# differential-buffer-quadchannel.net
KiCad netlist of a schematic drawn in EAGLE
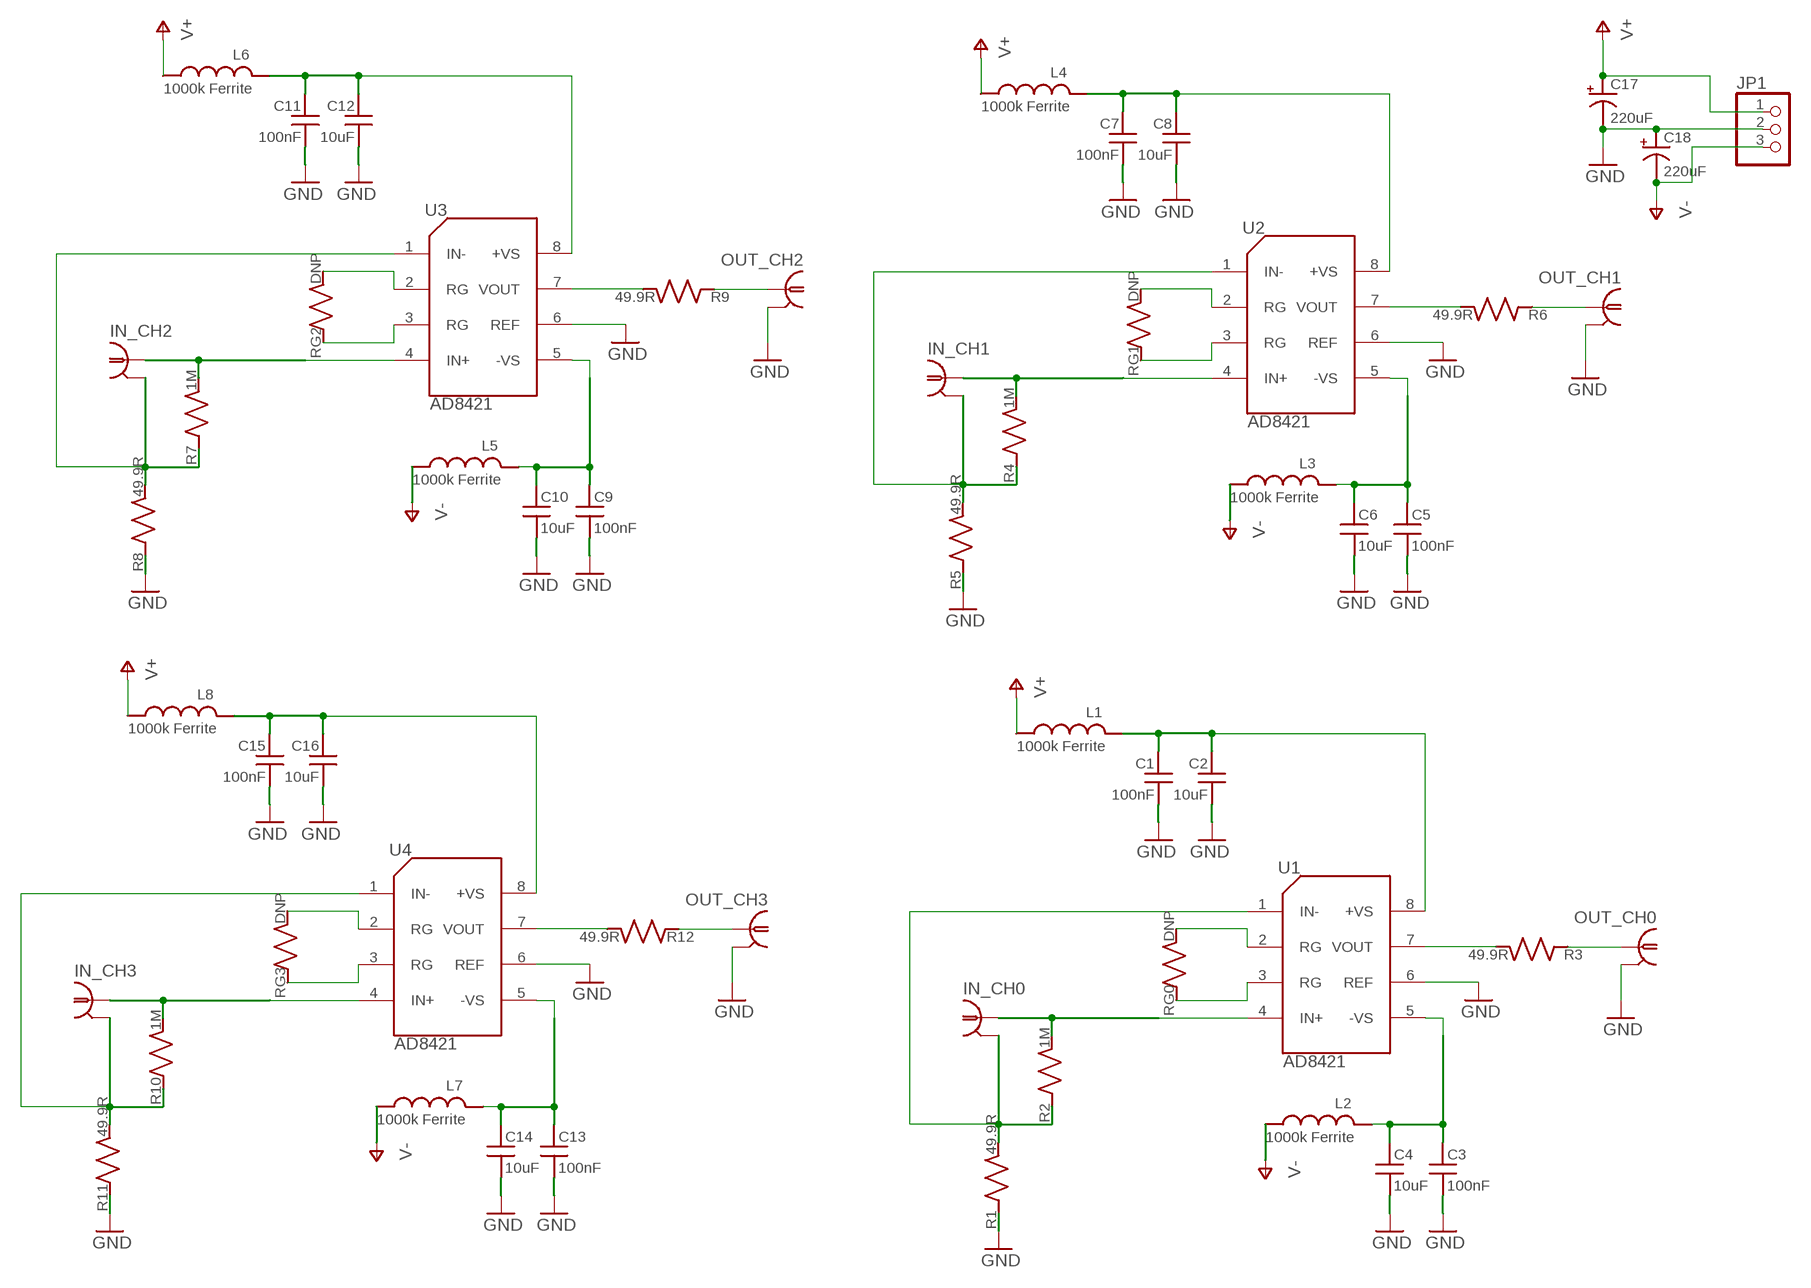
[diagram p0: schematic, sheet 1]

(export (version "E")
  (design (tool "Eeschema 10.0.6"))
  (components
    (comp (ref "C1")
      (value "100nF")
      (footprint "eagle-import:C_MLCC_0603")
      (fields (field (name "PARTNO") "1276-1936-1-ND"))
      (libsource (lib "eagle-import") (part "C_MLCC_SMDCMLCC_0603"))
    )
    (comp (ref "C2")
      (value "10uF")
      (footprint "eagle-import:C_MLCC_0805")
      (fields (field (name "PARTNO") "445-14417-1-ND"))
      (libsource (lib "eagle-import") (part "C_MLCC_SMDCMLCC_0805"))
    )
    (comp (ref "C3")
      (value "100nF")
      (footprint "eagle-import:C_MLCC_0603")
      (fields (field (name "PARTNO") "1276-1936-1-ND"))
      (libsource (lib "eagle-import") (part "C_MLCC_SMDCMLCC_0603"))
    )
    (comp (ref "C4")
      (value "10uF")
      (footprint "eagle-import:C_MLCC_0805")
      (fields (field (name "PARTNO") "445-14417-1-ND"))
      (libsource (lib "eagle-import") (part "C_MLCC_SMDCMLCC_0805"))
    )
    (comp (ref "C5")
      (value "100nF")
      (footprint "eagle-import:C_MLCC_0603")
      (fields (field (name "PARTNO") "1276-1936-1-ND"))
      (libsource (lib "eagle-import") (part "C_MLCC_SMDCMLCC_0603"))
    )
    (comp (ref "C6")
      (value "10uF")
      (footprint "eagle-import:C_MLCC_0805")
      (fields (field (name "PARTNO") "445-14417-1-ND"))
      (libsource (lib "eagle-import") (part "C_MLCC_SMDCMLCC_0805"))
    )
    (comp (ref "C7")
      (value "100nF")
      (footprint "eagle-import:C_MLCC_0603")
      (fields (field (name "PARTNO") "1276-1936-1-ND"))
      (libsource (lib "eagle-import") (part "C_MLCC_SMDCMLCC_0603"))
    )
    (comp (ref "C8")
      (value "10uF")
      (footprint "eagle-import:C_MLCC_0805")
      (fields (field (name "PARTNO") "445-14417-1-ND"))
      (libsource (lib "eagle-import") (part "C_MLCC_SMDCMLCC_0805"))
    )
    (comp (ref "C9")
      (value "100nF")
      (footprint "eagle-import:C_MLCC_0603")
      (fields (field (name "PARTNO") "1276-1936-1-ND"))
      (libsource (lib "eagle-import") (part "C_MLCC_SMDCMLCC_0603"))
    )
    (comp (ref "C10")
      (value "10uF")
      (footprint "eagle-import:C_MLCC_0805")
      (fields (field (name "PARTNO") "445-14417-1-ND"))
      (libsource (lib "eagle-import") (part "C_MLCC_SMDCMLCC_0805"))
    )
    (comp (ref "C11")
      (value "100nF")
      (footprint "eagle-import:C_MLCC_0603")
      (fields (field (name "PARTNO") "1276-1936-1-ND"))
      (libsource (lib "eagle-import") (part "C_MLCC_SMDCMLCC_0603"))
    )
    (comp (ref "C12")
      (value "10uF")
      (footprint "eagle-import:C_MLCC_0805")
      (fields (field (name "PARTNO") "445-14417-1-ND"))
      (libsource (lib "eagle-import") (part "C_MLCC_SMDCMLCC_0805"))
    )
    (comp (ref "C13")
      (value "100nF")
      (footprint "eagle-import:C_MLCC_0603")
      (fields (field (name "PARTNO") "1276-1936-1-ND"))
      (libsource (lib "eagle-import") (part "C_MLCC_SMDCMLCC_0603"))
    )
    (comp (ref "C14")
      (value "10uF")
      (footprint "eagle-import:C_MLCC_0805")
      (fields (field (name "PARTNO") "445-14417-1-ND"))
      (libsource (lib "eagle-import") (part "C_MLCC_SMDCMLCC_0805"))
    )
    (comp (ref "C15")
      (value "100nF")
      (footprint "eagle-import:C_MLCC_0603")
      (fields (field (name "PARTNO") "1276-1936-1-ND"))
      (libsource (lib "eagle-import") (part "C_MLCC_SMDCMLCC_0603"))
    )
    (comp (ref "C16")
      (value "10uF")
      (footprint "eagle-import:C_MLCC_0805")
      (fields (field (name "PARTNO") "445-14417-1-ND"))
      (libsource (lib "eagle-import") (part "C_MLCC_SMDCMLCC_0805"))
    )
    (comp (ref "C17")
      (value "220uF")
      (footprint "eagle-import:PANASONIC_F")
      (fields (field (name "PARTNO") "PCE3955CT-ND"))
      (libsource (lib "eagle-import") (part "C_POL_SMDF"))
    )
    (comp (ref "C18")
      (value "220uF")
      (footprint "eagle-import:PANASONIC_F")
      (fields (field (name "PARTNO") "PCE3955CT-ND"))
      (libsource (lib "eagle-import") (part "C_POL_SMDF"))
    )
    (comp (ref "IN_CH0")
      (value "BNC-V")
      (footprint "eagle-import:BNC-V")
      (libsource (lib "eagle-import") (part "BNC-V"))
    )
    (comp (ref "IN_CH1")
      (value "BNC-V")
      (footprint "eagle-import:BNC-V")
      (libsource (lib "eagle-import") (part "BNC-V"))
    )
    (comp (ref "IN_CH2")
      (value "BNC-V")
      (footprint "eagle-import:BNC-V")
      (libsource (lib "eagle-import") (part "BNC-V"))
    )
    (comp (ref "IN_CH3")
      (value "BNC-V")
      (footprint "eagle-import:BNC-V")
      (libsource (lib "eagle-import") (part "BNC-V"))
    )
    (comp (ref "JP1")
      (value "PINHD-1X3")
      (footprint "eagle-import:1X03")
      (fields (field (name "PARTNO") "WM4201-ND"))
      (libsource (lib "eagle-import") (part "PINHD-1X3"))
    )
    (comp (ref "L1")
      (value "1000k Ferrite")
      (footprint "eagle-import:L_FERRITE_0603")
      (fields (field (name "PARTNO") "445-1548-1-ND"))
      (libsource (lib "eagle-import") (part "L_FERRITE_SMDLFERRITE_0603"))
    )
    (comp (ref "L2")
      (value "1000k Ferrite")
      (footprint "eagle-import:L_FERRITE_0603")
      (fields (field (name "PARTNO") "445-1548-1-ND"))
      (libsource (lib "eagle-import") (part "L_FERRITE_SMDLFERRITE_0603"))
    )
    (comp (ref "L3")
      (value "1000k Ferrite")
      (footprint "eagle-import:L_FERRITE_0603")
      (fields (field (name "PARTNO") "445-1548-1-ND"))
      (libsource (lib "eagle-import") (part "L_FERRITE_SMDLFERRITE_0603"))
    )
    (comp (ref "L4")
      (value "1000k Ferrite")
      (footprint "eagle-import:L_FERRITE_0603")
      (fields (field (name "PARTNO") "445-1548-1-ND"))
      (libsource (lib "eagle-import") (part "L_FERRITE_SMDLFERRITE_0603"))
    )
    (comp (ref "L5")
      (value "1000k Ferrite")
      (footprint "eagle-import:L_FERRITE_0603")
      (fields (field (name "PARTNO") "445-1548-1-ND"))
      (libsource (lib "eagle-import") (part "L_FERRITE_SMDLFERRITE_0603"))
    )
    (comp (ref "L6")
      (value "1000k Ferrite")
      (footprint "eagle-import:L_FERRITE_0603")
      (fields (field (name "PARTNO") "445-1548-1-ND"))
      (libsource (lib "eagle-import") (part "L_FERRITE_SMDLFERRITE_0603"))
    )
    (comp (ref "L7")
      (value "1000k Ferrite")
      (footprint "eagle-import:L_FERRITE_0603")
      (fields (field (name "PARTNO") "445-1548-1-ND"))
      (libsource (lib "eagle-import") (part "L_FERRITE_SMDLFERRITE_0603"))
    )
    (comp (ref "L8")
      (value "1000k Ferrite")
      (footprint "eagle-import:L_FERRITE_0603")
      (fields (field (name "PARTNO") "445-1548-1-ND"))
      (libsource (lib "eagle-import") (part "L_FERRITE_SMDLFERRITE_0603"))
    )
    (comp (ref "OUT_CH0")
      (value "BNC-V")
      (footprint "eagle-import:BNC-V")
      (libsource (lib "eagle-import") (part "BNC-V"))
    )
    (comp (ref "OUT_CH1")
      (value "BNC-V")
      (footprint "eagle-import:BNC-V")
      (libsource (lib "eagle-import") (part "BNC-V"))
    )
    (comp (ref "OUT_CH2")
      (value "BNC-V")
      (footprint "eagle-import:BNC-V")
      (libsource (lib "eagle-import") (part "BNC-V"))
    )
    (comp (ref "OUT_CH3")
      (value "BNC-V")
      (footprint "eagle-import:BNC-V")
      (libsource (lib "eagle-import") (part "BNC-V"))
    )
    (comp (ref "R1")
      (value "49.9R")
      (footprint "eagle-import:R_0603")
      (fields (field (name "PARTNO") "P49.9HCT-ND"))
      (libsource (lib "eagle-import") (part "jqi_passives_R_SMDR0603"))
    )
    (comp (ref "R2")
      (value "1M")
      (footprint "eagle-import:R_0603")
      (fields (field (name "PARTNO") "P1.00MHCT-ND"))
      (libsource (lib "eagle-import") (part "R_SMDR0603"))
    )
    (comp (ref "R3")
      (value "49.9R")
      (footprint "eagle-import:R_0603")
      (fields (field (name "PARTNO") "P49.9HCT-ND"))
      (libsource (lib "eagle-import") (part "jqi_passives_R_SMDR0603"))
    )
    (comp (ref "R4")
      (value "1M")
      (footprint "eagle-import:R_0603")
      (fields (field (name "PARTNO") "P1.00MHCT-ND"))
      (libsource (lib "eagle-import") (part "R_SMDR0603"))
    )
    (comp (ref "R5")
      (value "49.9R")
      (footprint "eagle-import:R_0603")
      (fields (field (name "PARTNO") "P49.9HCT-ND"))
      (libsource (lib "eagle-import") (part "jqi_passives_R_SMDR0603"))
    )
    (comp (ref "R6")
      (value "49.9R")
      (footprint "eagle-import:R_0603")
      (fields (field (name "PARTNO") "P49.9HCT-ND"))
      (libsource (lib "eagle-import") (part "jqi_passives_R_SMDR0603"))
    )
    (comp (ref "R7")
      (value "1M")
      (footprint "eagle-import:R_0603")
      (fields (field (name "PARTNO") "P1.00MHCT-ND"))
      (libsource (lib "eagle-import") (part "R_SMDR0603"))
    )
    (comp (ref "R8")
      (value "49.9R")
      (footprint "eagle-import:R_0603")
      (fields (field (name "PARTNO") "P49.9HCT-ND"))
      (libsource (lib "eagle-import") (part "jqi_passives_R_SMDR0603"))
    )
    (comp (ref "R9")
      (value "49.9R")
      (footprint "eagle-import:R_0603")
      (fields (field (name "PARTNO") "P49.9HCT-ND"))
      (libsource (lib "eagle-import") (part "jqi_passives_R_SMDR0603"))
    )
    (comp (ref "R10")
      (value "1M")
      (footprint "eagle-import:R_0603")
      (fields (field (name "PARTNO") "P1.00MHCT-ND"))
      (libsource (lib "eagle-import") (part "R_SMDR0603"))
    )
    (comp (ref "R11")
      (value "49.9R")
      (footprint "eagle-import:R_0603")
      (fields (field (name "PARTNO") "P49.9HCT-ND"))
      (libsource (lib "eagle-import") (part "jqi_passives_R_SMDR0603"))
    )
    (comp (ref "R12")
      (value "49.9R")
      (footprint "eagle-import:R_0603")
      (fields (field (name "PARTNO") "P49.9HCT-ND"))
      (libsource (lib "eagle-import") (part "jqi_passives_R_SMDR0603"))
    )
    (comp (ref "RG0")
      (value "DNP")
      (footprint "eagle-import:R_0402")
      (libsource (lib "eagle-import") (part "jqi_passives_R_SMDR0402"))
    )
    (comp (ref "RG1")
      (value "DNP")
      (footprint "eagle-import:R_0402")
      (libsource (lib "eagle-import") (part "jqi_passives_R_SMDR0402"))
    )
    (comp (ref "RG2")
      (value "DNP")
      (footprint "eagle-import:R_0402")
      (libsource (lib "eagle-import") (part "jqi_passives_R_SMDR0402"))
    )
    (comp (ref "RG3")
      (value "DNP")
      (footprint "eagle-import:R_0402")
      (libsource (lib "eagle-import") (part "jqi_passives_R_SMDR0402"))
    )
    (comp (ref "U1")
      (value "AD8421")
      (footprint "eagle-import:SOIC-8")
      (fields (field (name "PARTNO") "AD8421ARZ-R7CT-ND"))
      (libsource (lib "eagle-import") (part "AD8421"))
    )
    (comp (ref "U2")
      (value "AD8421")
      (footprint "eagle-import:SOIC-8")
      (fields (field (name "PARTNO") "AD8421ARZ-R7CT-ND"))
      (libsource (lib "eagle-import") (part "AD8421"))
    )
    (comp (ref "U3")
      (value "AD8421")
      (footprint "eagle-import:SOIC-8")
      (fields (field (name "PARTNO") "AD8421ARZ-R7CT-ND"))
      (libsource (lib "eagle-import") (part "AD8421"))
    )
    (comp (ref "U4")
      (value "AD8421")
      (footprint "eagle-import:SOIC-8")
      (fields (field (name "PARTNO") "AD8421ARZ-R7CT-ND"))
      (libsource (lib "eagle-import") (part "AD8421"))
    )
  )
  (nets
    (net (code "1") (name "GND") (class "Default")
      (node (ref "C1") (pin "P$2") (pinfunction "2_P$2") (pintype "passive"))
      (node (ref "C10") (pin "P$2") (pinfunction "2_P$2") (pintype "passive"))
      (node (ref "C11") (pin "P$2") (pinfunction "2_P$2") (pintype "passive"))
      (node (ref "C12") (pin "P$2") (pinfunction "2_P$2") (pintype "passive"))
      (node (ref "C13") (pin "P$2") (pinfunction "2_P$2") (pintype "passive"))
      (node (ref "C14") (pin "P$2") (pinfunction "2_P$2") (pintype "passive"))
      (node (ref "C15") (pin "P$2") (pinfunction "2_P$2") (pintype "passive"))
      (node (ref "C16") (pin "P$2") (pinfunction "2_P$2") (pintype "passive"))
      (node (ref "C17") (pin "-") (pinfunction "-_-") (pintype "passive"))
      (node (ref "C18") (pin "+") (pinfunction "+_+") (pintype "passive"))
      (node (ref "C2") (pin "P$2") (pinfunction "2_P$2") (pintype "passive"))
      (node (ref "C3") (pin "P$2") (pinfunction "2_P$2") (pintype "passive"))
      (node (ref "C4") (pin "P$2") (pinfunction "2_P$2") (pintype "passive"))
      (node (ref "C5") (pin "P$2") (pinfunction "2_P$2") (pintype "passive"))
      (node (ref "C6") (pin "P$2") (pinfunction "2_P$2") (pintype "passive"))
      (node (ref "C7") (pin "P$2") (pinfunction "2_P$2") (pintype "passive"))
      (node (ref "C8") (pin "P$2") (pinfunction "2_P$2") (pintype "passive"))
      (node (ref "C9") (pin "P$2") (pinfunction "2_P$2") (pintype "passive"))
      (node (ref "JP1") (pin "2") (pinfunction "2_2") (pintype "passive"))
      (node (ref "OUT_CH0") (pin "2") (pinfunction "2_2") (pintype "passive"))
      (node (ref "OUT_CH1") (pin "2") (pinfunction "2_2") (pintype "passive"))
      (node (ref "OUT_CH2") (pin "2") (pinfunction "2_2") (pintype "passive"))
      (node (ref "OUT_CH3") (pin "2") (pinfunction "2_2") (pintype "passive"))
      (node (ref "R1") (pin "P$1") (pinfunction "1_P$1") (pintype "passive"))
      (node (ref "R11") (pin "P$1") (pinfunction "1_P$1") (pintype "passive"))
      (node (ref "R5") (pin "P$1") (pinfunction "1_P$1") (pintype "passive"))
      (node (ref "R8") (pin "P$1") (pinfunction "1_P$1") (pintype "passive"))
      (node (ref "U1") (pin "6") (pinfunction "REF_6") (pintype "bidirectional"))
      (node (ref "U2") (pin "6") (pinfunction "REF_6") (pintype "bidirectional"))
      (node (ref "U3") (pin "6") (pinfunction "REF_6") (pintype "bidirectional"))
      (node (ref "U4") (pin "6") (pinfunction "REF_6") (pintype "bidirectional"))
    )
    (net (code "2") (name "Net-(C1-1)") (class "Default")
      (node (ref "C1") (pin "P$1") (pinfunction "1_P$1") (pintype "passive"))
      (node (ref "C2") (pin "P$1") (pinfunction "1_P$1") (pintype "passive"))
      (node (ref "L1") (pin "P$1") (pinfunction "1_P$1") (pintype "passive"))
      (node (ref "U1") (pin "8") (pinfunction "+VS_8") (pintype "bidirectional"))
    )
    (net (code "3") (name "Net-(C3-1)") (class "Default")
      (node (ref "C3") (pin "P$1") (pinfunction "1_P$1") (pintype "passive"))
      (node (ref "C4") (pin "P$1") (pinfunction "1_P$1") (pintype "passive"))
      (node (ref "L2") (pin "P$1") (pinfunction "1_P$1") (pintype "passive"))
      (node (ref "U1") (pin "5") (pinfunction "-VS_5") (pintype "bidirectional"))
    )
    (net (code "4") (name "Net-(C5-1)") (class "Default")
      (node (ref "C5") (pin "P$1") (pinfunction "1_P$1") (pintype "passive"))
      (node (ref "C6") (pin "P$1") (pinfunction "1_P$1") (pintype "passive"))
      (node (ref "L3") (pin "P$1") (pinfunction "1_P$1") (pintype "passive"))
      (node (ref "U2") (pin "5") (pinfunction "-VS_5") (pintype "bidirectional"))
    )
    (net (code "5") (name "Net-(C7-1)") (class "Default")
      (node (ref "C7") (pin "P$1") (pinfunction "1_P$1") (pintype "passive"))
      (node (ref "C8") (pin "P$1") (pinfunction "1_P$1") (pintype "passive"))
      (node (ref "L4") (pin "P$1") (pinfunction "1_P$1") (pintype "passive"))
      (node (ref "U2") (pin "8") (pinfunction "+VS_8") (pintype "bidirectional"))
    )
    (net (code "6") (name "Net-(C10-1)") (class "Default")
      (node (ref "C10") (pin "P$1") (pinfunction "1_P$1") (pintype "passive"))
      (node (ref "C9") (pin "P$1") (pinfunction "1_P$1") (pintype "passive"))
      (node (ref "L5") (pin "P$1") (pinfunction "1_P$1") (pintype "passive"))
      (node (ref "U3") (pin "5") (pinfunction "-VS_5") (pintype "bidirectional"))
    )
    (net (code "7") (name "Net-(C11-1)") (class "Default")
      (node (ref "C11") (pin "P$1") (pinfunction "1_P$1") (pintype "passive"))
      (node (ref "C12") (pin "P$1") (pinfunction "1_P$1") (pintype "passive"))
      (node (ref "L6") (pin "P$1") (pinfunction "1_P$1") (pintype "passive"))
      (node (ref "U3") (pin "8") (pinfunction "+VS_8") (pintype "bidirectional"))
    )
    (net (code "8") (name "Net-(C13-1)") (class "Default")
      (node (ref "C13") (pin "P$1") (pinfunction "1_P$1") (pintype "passive"))
      (node (ref "C14") (pin "P$1") (pinfunction "1_P$1") (pintype "passive"))
      (node (ref "L7") (pin "P$1") (pinfunction "1_P$1") (pintype "passive"))
      (node (ref "U4") (pin "5") (pinfunction "-VS_5") (pintype "bidirectional"))
    )
    (net (code "9") (name "Net-(C15-1)") (class "Default")
      (node (ref "C15") (pin "P$1") (pinfunction "1_P$1") (pintype "passive"))
      (node (ref "C16") (pin "P$1") (pinfunction "1_P$1") (pintype "passive"))
      (node (ref "L8") (pin "P$1") (pinfunction "1_P$1") (pintype "passive"))
      (node (ref "U4") (pin "8") (pinfunction "+VS_8") (pintype "bidirectional"))
    )
    (net (code "10") (name "Net-(R1-2)") (class "Default")
      (node (ref "IN_CH0") (pin "2") (pinfunction "2_2") (pintype "passive"))
      (node (ref "R1") (pin "P$2") (pinfunction "2_P$2") (pintype "passive"))
      (node (ref "R2") (pin "P$1") (pinfunction "1_P$1") (pintype "passive"))
      (node (ref "U1") (pin "1") (pinfunction "IN-_1") (pintype "bidirectional"))
    )
    (net (code "11") (name "Net-(R2-2)") (class "Default")
      (node (ref "IN_CH0") (pin "1") (pinfunction "1_1") (pintype "passive"))
      (node (ref "R2") (pin "P$2") (pinfunction "2_P$2") (pintype "passive"))
      (node (ref "U1") (pin "4") (pinfunction "IN+_4") (pintype "bidirectional"))
    )
    (net (code "12") (name "Net-(R3-1)") (class "Default")
      (node (ref "OUT_CH0") (pin "1") (pinfunction "1_1") (pintype "passive"))
      (node (ref "R3") (pin "P$1") (pinfunction "1_P$1") (pintype "passive"))
    )
    (net (code "13") (name "Net-(R3-2)") (class "Default")
      (node (ref "R3") (pin "P$2") (pinfunction "2_P$2") (pintype "passive"))
      (node (ref "U1") (pin "7") (pinfunction "VOUT_7") (pintype "bidirectional"))
    )
    (net (code "14") (name "Net-(R4-1)") (class "Default")
      (node (ref "IN_CH1") (pin "2") (pinfunction "2_2") (pintype "passive"))
      (node (ref "R4") (pin "P$1") (pinfunction "1_P$1") (pintype "passive"))
      (node (ref "R5") (pin "P$2") (pinfunction "2_P$2") (pintype "passive"))
      (node (ref "U2") (pin "1") (pinfunction "IN-_1") (pintype "bidirectional"))
    )
    (net (code "15") (name "Net-(R4-2)") (class "Default")
      (node (ref "IN_CH1") (pin "1") (pinfunction "1_1") (pintype "passive"))
      (node (ref "R4") (pin "P$2") (pinfunction "2_P$2") (pintype "passive"))
      (node (ref "U2") (pin "4") (pinfunction "IN+_4") (pintype "bidirectional"))
    )
    (net (code "16") (name "Net-(R6-1)") (class "Default")
      (node (ref "OUT_CH1") (pin "1") (pinfunction "1_1") (pintype "passive"))
      (node (ref "R6") (pin "P$1") (pinfunction "1_P$1") (pintype "passive"))
    )
    (net (code "17") (name "Net-(R6-2)") (class "Default")
      (node (ref "R6") (pin "P$2") (pinfunction "2_P$2") (pintype "passive"))
      (node (ref "U2") (pin "7") (pinfunction "VOUT_7") (pintype "bidirectional"))
    )
    (net (code "18") (name "Net-(R7-1)") (class "Default")
      (node (ref "IN_CH2") (pin "2") (pinfunction "2_2") (pintype "passive"))
      (node (ref "R7") (pin "P$1") (pinfunction "1_P$1") (pintype "passive"))
      (node (ref "R8") (pin "P$2") (pinfunction "2_P$2") (pintype "passive"))
      (node (ref "U3") (pin "1") (pinfunction "IN-_1") (pintype "bidirectional"))
    )
    (net (code "19") (name "Net-(R7-2)") (class "Default")
      (node (ref "IN_CH2") (pin "1") (pinfunction "1_1") (pintype "passive"))
      (node (ref "R7") (pin "P$2") (pinfunction "2_P$2") (pintype "passive"))
      (node (ref "U3") (pin "4") (pinfunction "IN+_4") (pintype "bidirectional"))
    )
    (net (code "20") (name "Net-(R9-1)") (class "Default")
      (node (ref "OUT_CH2") (pin "1") (pinfunction "1_1") (pintype "passive"))
      (node (ref "R9") (pin "P$1") (pinfunction "1_P$1") (pintype "passive"))
    )
    (net (code "21") (name "Net-(R9-2)") (class "Default")
      (node (ref "R9") (pin "P$2") (pinfunction "2_P$2") (pintype "passive"))
      (node (ref "U3") (pin "7") (pinfunction "VOUT_7") (pintype "bidirectional"))
    )
    (net (code "22") (name "Net-(R10-1)") (class "Default")
      (node (ref "IN_CH3") (pin "2") (pinfunction "2_2") (pintype "passive"))
      (node (ref "R10") (pin "P$1") (pinfunction "1_P$1") (pintype "passive"))
      (node (ref "R11") (pin "P$2") (pinfunction "2_P$2") (pintype "passive"))
      (node (ref "U4") (pin "1") (pinfunction "IN-_1") (pintype "bidirectional"))
    )
    (net (code "23") (name "Net-(R10-2)") (class "Default")
      (node (ref "IN_CH3") (pin "1") (pinfunction "1_1") (pintype "passive"))
      (node (ref "R10") (pin "P$2") (pinfunction "2_P$2") (pintype "passive"))
      (node (ref "U4") (pin "4") (pinfunction "IN+_4") (pintype "bidirectional"))
    )
    (net (code "24") (name "Net-(R12-1)") (class "Default")
      (node (ref "OUT_CH3") (pin "1") (pinfunction "1_1") (pintype "passive"))
      (node (ref "R12") (pin "P$1") (pinfunction "1_P$1") (pintype "passive"))
    )
    (net (code "25") (name "Net-(R12-2)") (class "Default")
      (node (ref "R12") (pin "P$2") (pinfunction "2_P$2") (pintype "passive"))
      (node (ref "U4") (pin "7") (pinfunction "VOUT_7") (pintype "bidirectional"))
    )
    (net (code "26") (name "Net-(RG0-1)") (class "Default")
      (node (ref "RG0") (pin "P$1") (pinfunction "1_P$1") (pintype "passive"))
      (node (ref "U1") (pin "3") (pinfunction "RG_3") (pintype "bidirectional"))
    )
    (net (code "27") (name "Net-(RG0-2)") (class "Default")
      (node (ref "RG0") (pin "P$2") (pinfunction "2_P$2") (pintype "passive"))
      (node (ref "U1") (pin "2") (pinfunction "RG_2") (pintype "bidirectional"))
    )
    (net (code "28") (name "Net-(RG1-1)") (class "Default")
      (node (ref "RG1") (pin "P$1") (pinfunction "1_P$1") (pintype "passive"))
      (node (ref "U2") (pin "3") (pinfunction "RG_3") (pintype "bidirectional"))
    )
    (net (code "29") (name "Net-(RG1-2)") (class "Default")
      (node (ref "RG1") (pin "P$2") (pinfunction "2_P$2") (pintype "passive"))
      (node (ref "U2") (pin "2") (pinfunction "RG_2") (pintype "bidirectional"))
    )
    (net (code "30") (name "Net-(RG2-1)") (class "Default")
      (node (ref "RG2") (pin "P$1") (pinfunction "1_P$1") (pintype "passive"))
      (node (ref "U3") (pin "3") (pinfunction "RG_3") (pintype "bidirectional"))
    )
    (net (code "31") (name "Net-(RG2-2)") (class "Default")
      (node (ref "RG2") (pin "P$2") (pinfunction "2_P$2") (pintype "passive"))
      (node (ref "U3") (pin "2") (pinfunction "RG_2") (pintype "bidirectional"))
    )
    (net (code "32") (name "Net-(RG3-1)") (class "Default")
      (node (ref "RG3") (pin "P$1") (pinfunction "1_P$1") (pintype "passive"))
      (node (ref "U4") (pin "3") (pinfunction "RG_3") (pintype "bidirectional"))
    )
    (net (code "33") (name "Net-(RG3-2)") (class "Default")
      (node (ref "RG3") (pin "P$2") (pinfunction "2_P$2") (pintype "passive"))
      (node (ref "U4") (pin "2") (pinfunction "RG_2") (pintype "bidirectional"))
    )
    (net (code "34") (name "V+") (class "Default")
      (node (ref "C17") (pin "+") (pinfunction "+_+") (pintype "passive"))
      (node (ref "JP1") (pin "1") (pinfunction "1_1") (pintype "passive"))
      (node (ref "L1") (pin "P$2") (pinfunction "2_P$2") (pintype "passive"))
      (node (ref "L4") (pin "P$2") (pinfunction "2_P$2") (pintype "passive"))
      (node (ref "L6") (pin "P$2") (pinfunction "2_P$2") (pintype "passive"))
      (node (ref "L8") (pin "P$2") (pinfunction "2_P$2") (pintype "passive"))
    )
    (net (code "35") (name "V-") (class "Default")
      (node (ref "C18") (pin "-") (pinfunction "-_-") (pintype "passive"))
      (node (ref "JP1") (pin "3") (pinfunction "3_3") (pintype "passive"))
      (node (ref "L2") (pin "P$2") (pinfunction "2_P$2") (pintype "passive"))
      (node (ref "L3") (pin "P$2") (pinfunction "2_P$2") (pintype "passive"))
      (node (ref "L5") (pin "P$2") (pinfunction "2_P$2") (pintype "passive"))
      (node (ref "L7") (pin "P$2") (pinfunction "2_P$2") (pintype "passive"))
    )
  )
)
